# RangkaianPSU12V___RangkaianStepdown5v.net
KiCad netlist of a schematic drawn in EAGLE
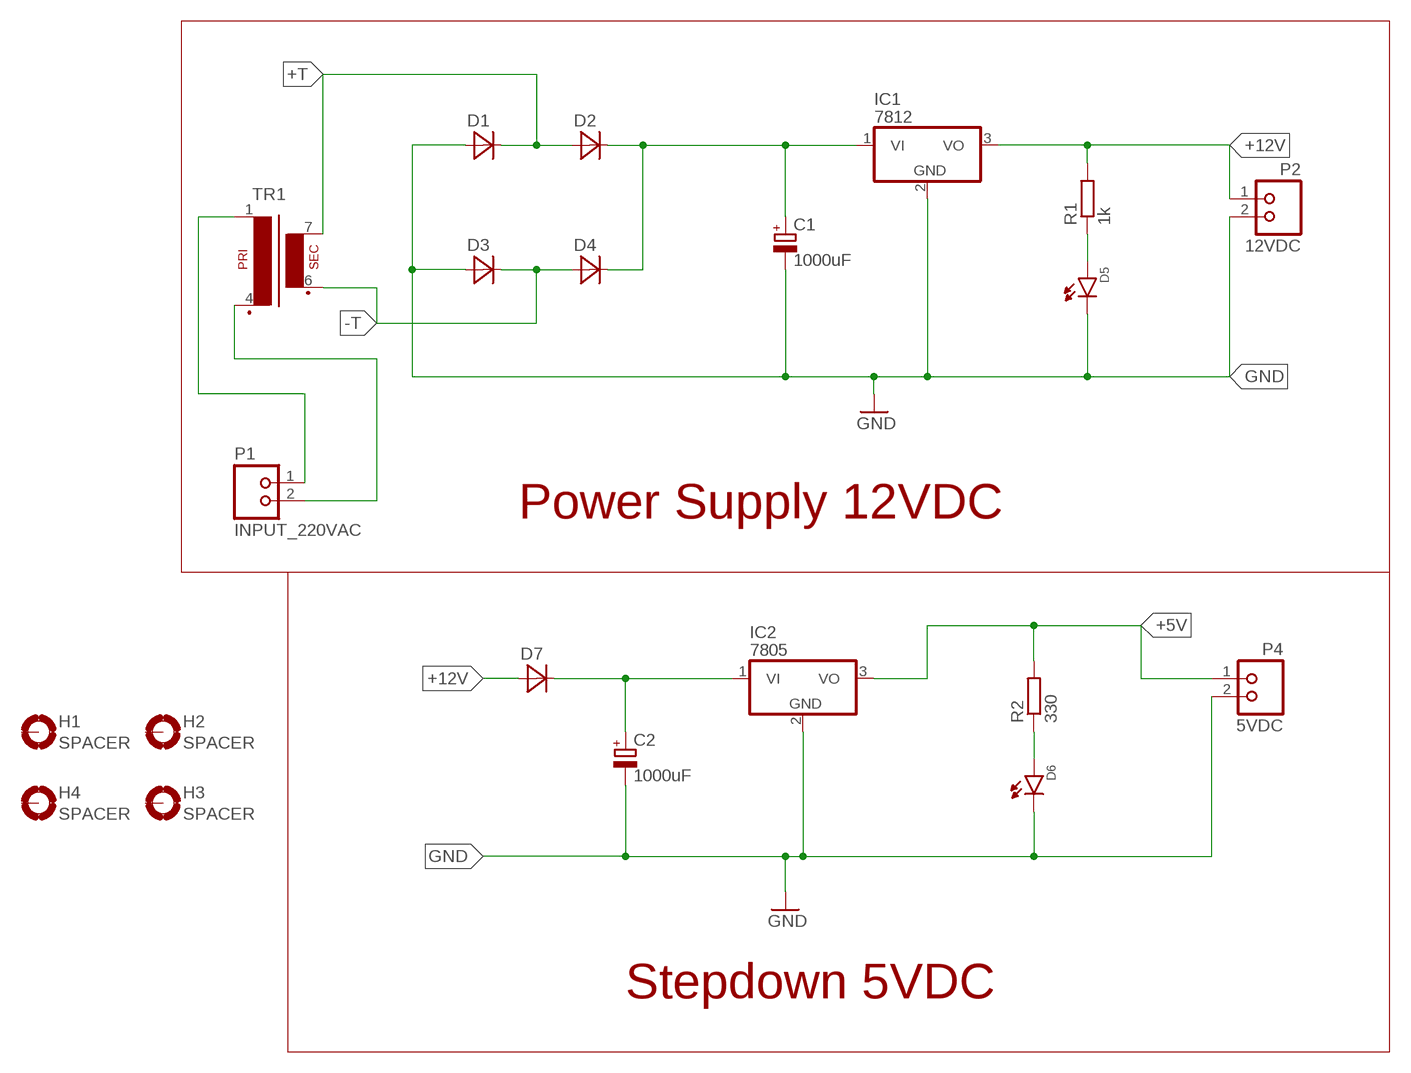
[diagram p0: schematic, sheet 1]

(export (version "E")
  (design (tool "Eeschema 10.0.6"))
  (components
    (comp (ref "C1")
      (value "1000uF")
      (footprint "eagle-import:E5-4")
      (libsource (lib "eagle-import") (part "CAPACITOR_POLARE5-4"))
    )
    (comp (ref "C2")
      (value "1000uF")
      (footprint "eagle-import:E5-4")
      (libsource (lib "eagle-import") (part "CAPACITOR_POLARE5-4"))
    )
    (comp (ref "D1")
      (value "1N4148")
      (footprint "eagle-import:DO35-10")
      (libsource (lib "eagle-import") (part "1N4148"))
    )
    (comp (ref "D2")
      (value "1N4148")
      (footprint "eagle-import:DO35-10")
      (libsource (lib "eagle-import") (part "1N4148"))
    )
    (comp (ref "D3")
      (value "1N4148")
      (footprint "eagle-import:DO35-10")
      (libsource (lib "eagle-import") (part "1N4148"))
    )
    (comp (ref "D4")
      (value "1N4148")
      (footprint "eagle-import:DO35-10")
      (libsource (lib "eagle-import") (part "1N4148"))
    )
    (comp (ref "D5")
      (value "LED-3MM")
      (footprint "eagle-import:LED")
      (libsource (lib "eagle-import") (part "LED-3MM"))
    )
    (comp (ref "D6")
      (value "LED-3MM")
      (footprint "eagle-import:LED")
      (libsource (lib "eagle-import") (part "LED-3MM"))
    )
    (comp (ref "D7")
      (value "1N4148")
      (footprint "eagle-import:DO35-10")
      (libsource (lib "eagle-import") (part "01_1N4148"))
    )
    (comp (ref "H1")
      (value "SPACER")
      (footprint "eagle-import:3,0-PAD")
      (libsource (lib "eagle-import") (part "SPACER"))
    )
    (comp (ref "H2")
      (value "SPACER")
      (footprint "eagle-import:3,0-PAD")
      (libsource (lib "eagle-import") (part "SPACER"))
    )
    (comp (ref "H3")
      (value "SPACER")
      (footprint "eagle-import:3,0-PAD")
      (libsource (lib "eagle-import") (part "SPACER"))
    )
    (comp (ref "H4")
      (value "SPACER")
      (footprint "eagle-import:3,0-PAD")
      (libsource (lib "eagle-import") (part "SPACER"))
    )
    (comp (ref "IC1")
      (value "7812")
      (footprint "eagle-import:TO220V")
      (libsource (lib "eagle-import") (part "78TV12"))
    )
    (comp (ref "IC2")
      (value "7805")
      (footprint "eagle-import:TO220V")
      (libsource (lib "eagle-import") (part "78TV05"))
    )
    (comp (ref "P1")
      (value "INPUT_220VAC")
      (footprint "eagle-import:TERMINAL_2P")
      (libsource (lib "eagle-import") (part "T-BLOCK"))
    )
    (comp (ref "P2")
      (value "12VDC")
      (footprint "eagle-import:TERMINAL_2P")
      (libsource (lib "eagle-import") (part "T-BLOCK"))
    )
    (comp (ref "P4")
      (value "5VDC")
      (footprint "eagle-import:TERMINAL_2P")
      (libsource (lib "eagle-import") (part "T-BLOCK"))
    )
    (comp (ref "R1")
      (value "1k")
      (footprint "eagle-import:AXIAL")
      (libsource (lib "eagle-import") (part "RESISTORAXIAL"))
    )
    (comp (ref "R2")
      (value "330")
      (footprint "eagle-import:AXIAL")
      (libsource (lib "eagle-import") (part "RESISTORAXIAL"))
    )
    (comp (ref "TR1")
      (value "EE20-1")
      (footprint "eagle-import:EE20-1")
      (libsource (lib "eagle-import") (part "EE20-1"))
    )
  )
  (nets
    (net (code "1") (name "+5V") (class "Default")
      (node (ref "IC2") (pin "3") (pinfunction "VO_3") (pintype "passive"))
      (node (ref "P4") (pin "1") (pinfunction "1_1") (pintype "passive"))
      (node (ref "R2") (pin "2") (pinfunction "2_2") (pintype "passive"))
    )
    (net (code "2") (name "+12V") (class "Default")
      (node (ref "D7") (pin "A") (pinfunction "A_A") (pintype "passive"))
      (node (ref "IC1") (pin "3") (pinfunction "VO_3") (pintype "passive"))
      (node (ref "P2") (pin "1") (pinfunction "1_1") (pintype "passive"))
      (node (ref "R1") (pin "2") (pinfunction "2_2") (pintype "passive"))
    )
    (net (code "3") (name "+T") (class "Default")
      (node (ref "D1") (pin "K") (pinfunction "K_K") (pintype "passive"))
      (node (ref "D2") (pin "A") (pinfunction "A_A") (pintype "passive"))
      (node (ref "TR1") (pin "7") (pinfunction "S4_7") (pintype "passive"))
    )
    (net (code "4") (name "-T") (class "Default")
      (node (ref "D3") (pin "K") (pinfunction "K_K") (pintype "passive"))
      (node (ref "D4") (pin "A") (pinfunction "A_A") (pintype "passive"))
      (node (ref "TR1") (pin "6") (pinfunction "S3_6") (pintype "passive"))
    )
    (net (code "5") (name "GND") (class "Default")
      (node (ref "C1") (pin "-") (pinfunction "-_-") (pintype "passive"))
      (node (ref "C2") (pin "-") (pinfunction "-_-") (pintype "passive"))
      (node (ref "D1") (pin "A") (pinfunction "A_A") (pintype "passive"))
      (node (ref "D3") (pin "A") (pinfunction "A_A") (pintype "passive"))
      (node (ref "D5") (pin "2") (pinfunction "2_2") (pintype "bidirectional"))
      (node (ref "D6") (pin "2") (pinfunction "2_2") (pintype "bidirectional"))
      (node (ref "IC1") (pin "2") (pinfunction "GND_2") (pintype "passive"))
      (node (ref "IC2") (pin "2") (pinfunction "GND_2") (pintype "passive"))
      (node (ref "P2") (pin "2") (pinfunction "2_2") (pintype "passive"))
      (node (ref "P4") (pin "2") (pinfunction "2_2") (pintype "passive"))
    )
    (net (code "6") (name "Net-(D5-Pad1)") (class "Default")
      (node (ref "D5") (pin "1") (pinfunction "1_1") (pintype "bidirectional"))
      (node (ref "R1") (pin "1") (pinfunction "1_1") (pintype "passive"))
    )
    (net (code "7") (name "Net-(D6-Pad1)") (class "Default")
      (node (ref "D6") (pin "1") (pinfunction "1_1") (pintype "bidirectional"))
      (node (ref "R2") (pin "1") (pinfunction "1_1") (pintype "passive"))
    )
    (net (code "8") (name "Net-(IC1-VI)") (class "Default")
      (node (ref "C1") (pin "+") (pinfunction "+_+") (pintype "passive"))
      (node (ref "D2") (pin "K") (pinfunction "K_K") (pintype "passive"))
      (node (ref "D4") (pin "K") (pinfunction "K_K") (pintype "passive"))
      (node (ref "IC1") (pin "1") (pinfunction "VI_1") (pintype "input"))
    )
    (net (code "9") (name "Net-(IC2-VI)") (class "Default")
      (node (ref "C2") (pin "+") (pinfunction "+_+") (pintype "passive"))
      (node (ref "D7") (pin "K") (pinfunction "K_K") (pintype "passive"))
      (node (ref "IC2") (pin "1") (pinfunction "VI_1") (pintype "input"))
    )
    (net (code "10") (name "Net-(TR1-P1)") (class "Default")
      (node (ref "P1") (pin "1") (pinfunction "1_1") (pintype "passive"))
      (node (ref "TR1") (pin "1") (pinfunction "P1_1") (pintype "passive"))
    )
    (net (code "11") (name "Net-(TR1-P2)") (class "Default")
      (node (ref "P1") (pin "2") (pinfunction "2_2") (pintype "passive"))
      (node (ref "TR1") (pin "4") (pinfunction "P2_4") (pintype "passive"))
    )
    (net (code "12") (name "unconnected-(H1-MOUNT-PadB3,0)") (class "Default")
      (node (ref "H1") (pin "B3,0") (pinfunction "MOUNT_B3,0") (pintype "passive"))
    )
    (net (code "13") (name "unconnected-(H2-MOUNT-PadB3,0)") (class "Default")
      (node (ref "H2") (pin "B3,0") (pinfunction "MOUNT_B3,0") (pintype "passive"))
    )
    (net (code "14") (name "unconnected-(H3-MOUNT-PadB3,0)") (class "Default")
      (node (ref "H3") (pin "B3,0") (pinfunction "MOUNT_B3,0") (pintype "passive"))
    )
    (net (code "15") (name "unconnected-(H4-MOUNT-PadB3,0)") (class "Default")
      (node (ref "H4") (pin "B3,0") (pinfunction "MOUNT_B3,0") (pintype "passive"))
    )
  )
)
